# IO.net
KiCad netlist of a schematic drawn in Altium Designer
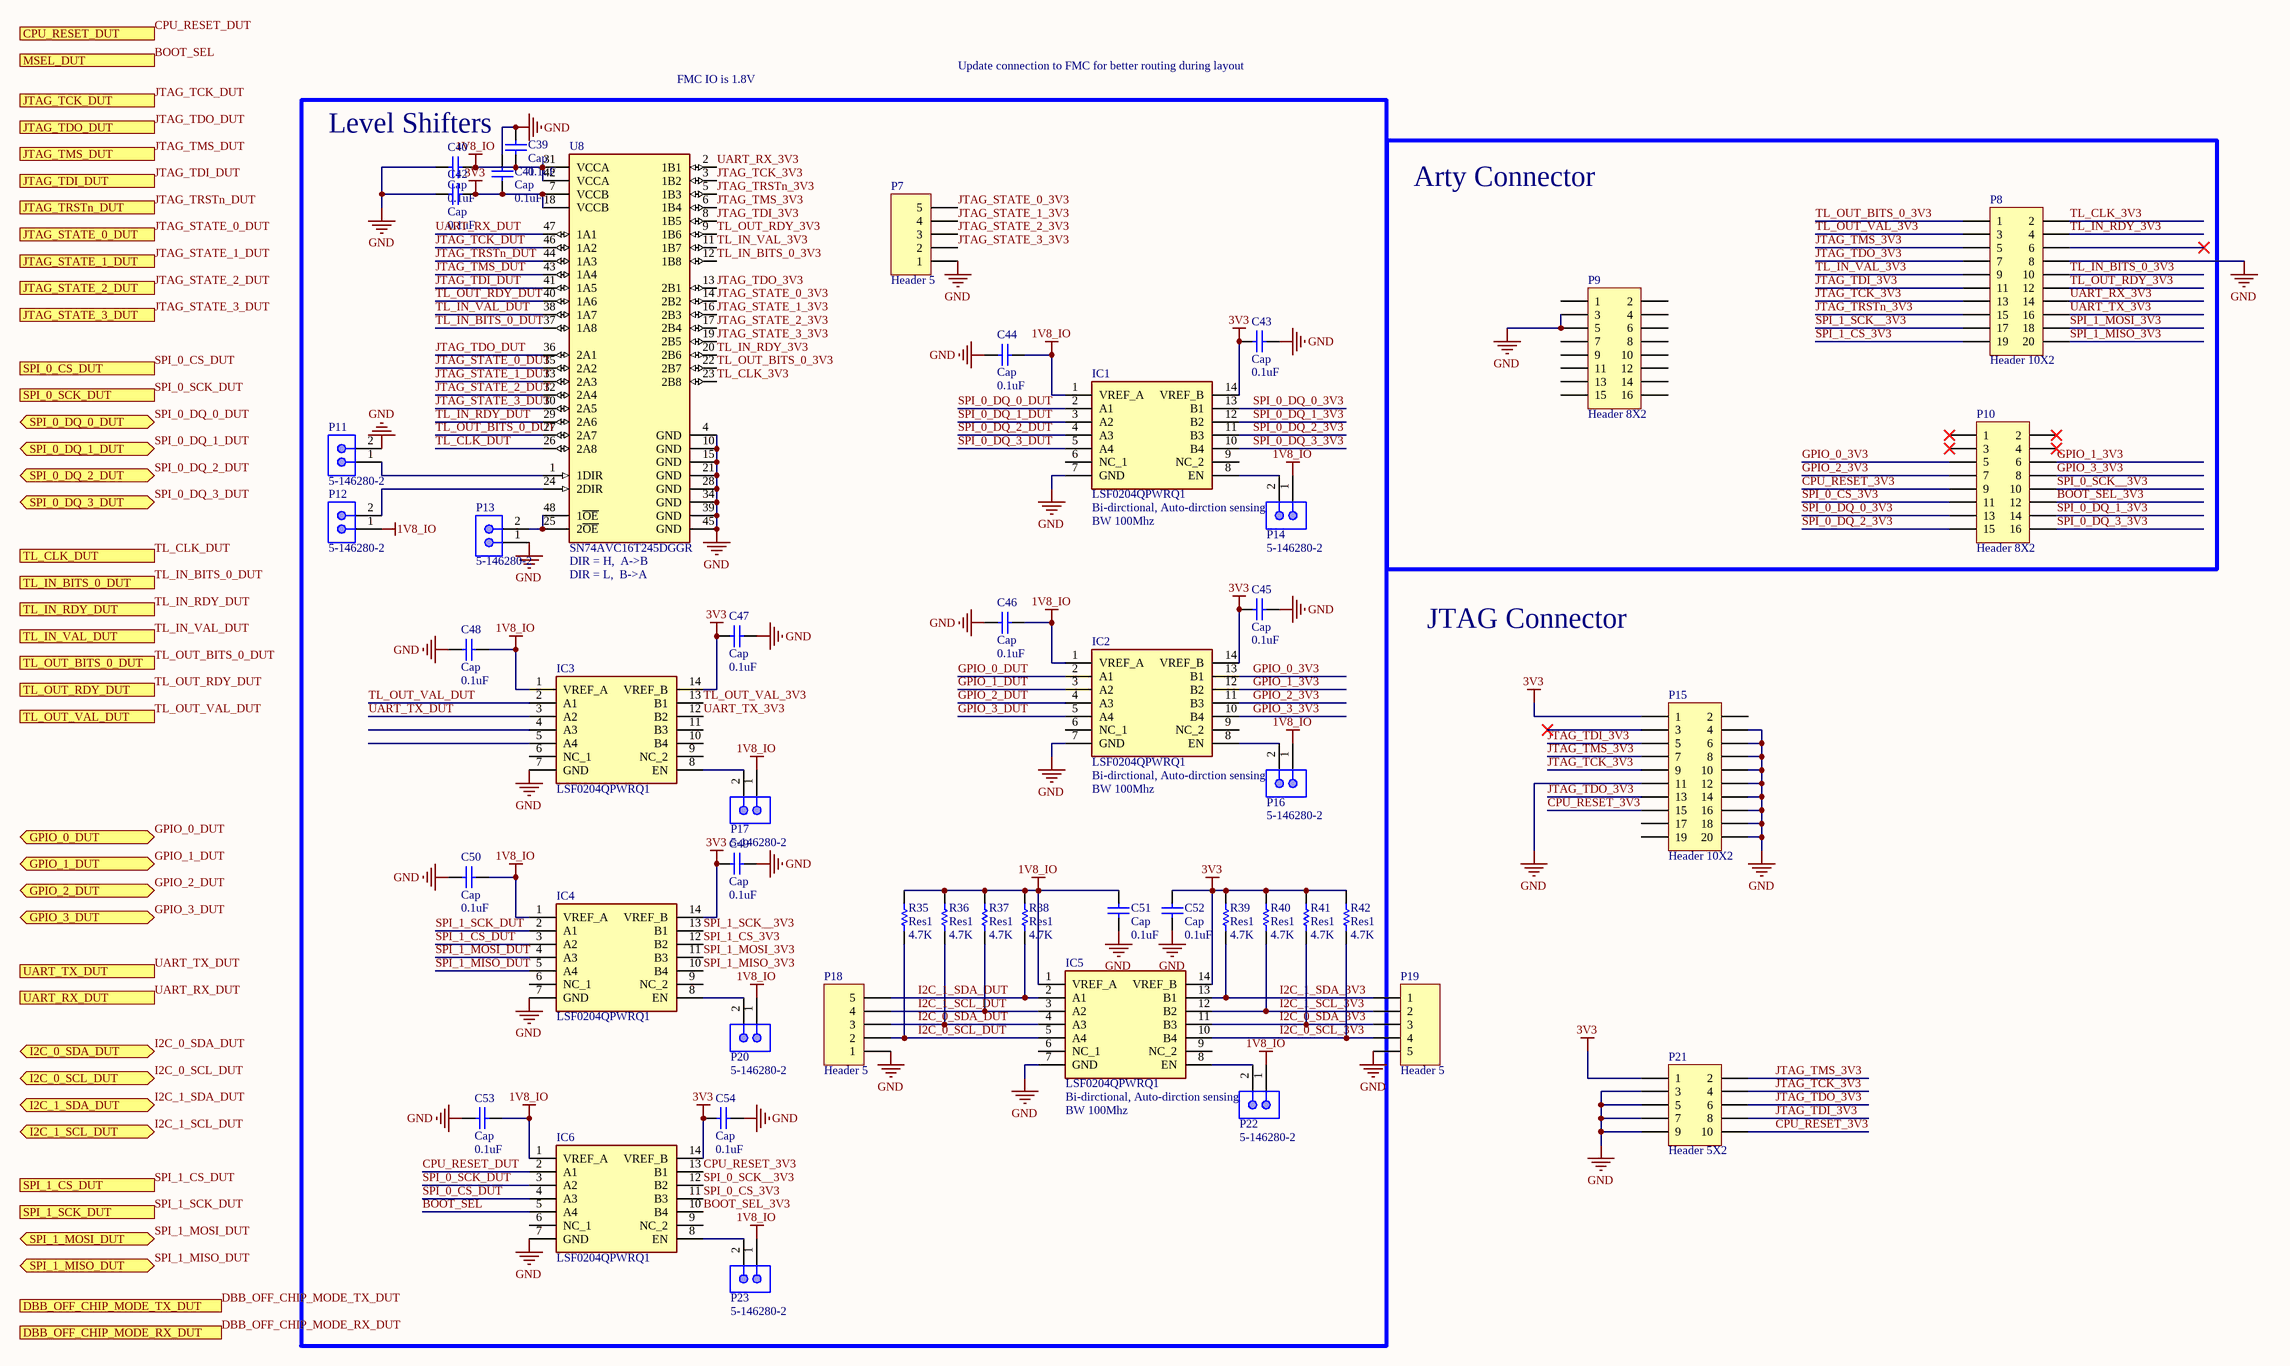
[diagram p0: IO.SchDoc]

(export (version "E")
  (design (tool "Eeschema 10.0.6"))
  (components
    (comp (ref "C39")
      (value "Cap")
      (footprint "0603")
      (description "Capacitor")
      (fields (field (name "ALTIUM_VALUE") "0.1uF") (field (name "PUBLISHER") "Altium Limited"))
      (libsource (lib "Miscellaneous Devices") (part "Cap"))
    )
    (comp (ref "C40")
      (value "Cap")
      (footprint "0603")
      (description "Capacitor")
      (fields (field (name "ALTIUM_VALUE") "0.1uF") (field (name "PUBLISHER") "Altium Limited"))
      (libsource (lib "Miscellaneous Devices") (part "Cap"))
    )
    (comp (ref "C41")
      (value "Cap")
      (footprint "0603")
      (description "Capacitor")
      (fields (field (name "ALTIUM_VALUE") "0.1uF") (field (name "PUBLISHER") "Altium Limited"))
      (libsource (lib "Miscellaneous Devices") (part "Cap"))
    )
    (comp (ref "C42")
      (value "Cap")
      (footprint "0603")
      (description "Capacitor")
      (fields (field (name "ALTIUM_VALUE") "0.1uF") (field (name "PUBLISHER") "Altium Limited"))
      (libsource (lib "Miscellaneous Devices") (part "Cap"))
    )
    (comp (ref "C43")
      (value "Cap")
      (footprint "0603")
      (description "Capacitor")
      (fields (field (name "ALTIUM_VALUE") "0.1uF") (field (name "PUBLISHER") "Altium Limited"))
      (libsource (lib "Miscellaneous Devices") (part "Cap"))
    )
    (comp (ref "C44")
      (value "Cap")
      (footprint "0603")
      (description "Capacitor")
      (fields (field (name "ALTIUM_VALUE") "0.1uF") (field (name "PUBLISHER") "Altium Limited"))
      (libsource (lib "Miscellaneous Devices") (part "Cap"))
    )
    (comp (ref "C45")
      (value "Cap")
      (footprint "0603")
      (description "Capacitor")
      (fields (field (name "ALTIUM_VALUE") "0.1uF") (field (name "PUBLISHER") "Altium Limited"))
      (libsource (lib "Miscellaneous Devices") (part "Cap"))
    )
    (comp (ref "C46")
      (value "Cap")
      (footprint "0603")
      (description "Capacitor")
      (fields (field (name "ALTIUM_VALUE") "0.1uF") (field (name "PUBLISHER") "Altium Limited"))
      (libsource (lib "Miscellaneous Devices") (part "Cap"))
    )
    (comp (ref "C47")
      (value "Cap")
      (footprint "0603")
      (description "Capacitor")
      (fields (field (name "ALTIUM_VALUE") "0.1uF") (field (name "PUBLISHER") "Altium Limited"))
      (libsource (lib "Miscellaneous Devices") (part "Cap"))
    )
    (comp (ref "C48")
      (value "Cap")
      (footprint "0603")
      (description "Capacitor")
      (fields (field (name "ALTIUM_VALUE") "0.1uF") (field (name "PUBLISHER") "Altium Limited"))
      (libsource (lib "Miscellaneous Devices") (part "Cap"))
    )
    (comp (ref "C49")
      (value "Cap")
      (footprint "0603")
      (description "Capacitor")
      (fields (field (name "ALTIUM_VALUE") "0.1uF") (field (name "PUBLISHER") "Altium Limited"))
      (libsource (lib "Miscellaneous Devices") (part "Cap"))
    )
    (comp (ref "C50")
      (value "Cap")
      (footprint "0603")
      (description "Capacitor")
      (fields (field (name "ALTIUM_VALUE") "0.1uF") (field (name "PUBLISHER") "Altium Limited"))
      (libsource (lib "Miscellaneous Devices") (part "Cap"))
    )
    (comp (ref "C51")
      (value "Cap")
      (footprint "0603")
      (description "Capacitor")
      (fields (field (name "ALTIUM_VALUE") "0.1uF") (field (name "PUBLISHER") "Altium Limited"))
      (libsource (lib "Miscellaneous Devices") (part "Cap"))
    )
    (comp (ref "C52")
      (value "Cap")
      (footprint "0603")
      (description "Capacitor")
      (fields (field (name "ALTIUM_VALUE") "0.1uF") (field (name "PUBLISHER") "Altium Limited"))
      (libsource (lib "Miscellaneous Devices") (part "Cap"))
    )
    (comp (ref "C53")
      (value "Cap")
      (footprint "0603")
      (description "Capacitor")
      (fields (field (name "ALTIUM_VALUE") "0.1uF") (field (name "PUBLISHER") "Altium Limited"))
      (libsource (lib "Miscellaneous Devices") (part "Cap"))
    )
    (comp (ref "C54")
      (value "Cap")
      (footprint "0603")
      (description "Capacitor")
      (fields (field (name "ALTIUM_VALUE") "0.1uF") (field (name "PUBLISHER") "Altium Limited"))
      (libsource (lib "Miscellaneous Devices") (part "Cap"))
    )
    (comp (ref "IC1")
      (value "LSF0204QPWRQ1")
      (footprint "SOP65P640X120-14N")
      (fields (field (name "MOUSER PART NUMBER") "595-LSF0204QPWRQ1"))
      (libsource (lib "EE194 Fall2022") (part "LSF0204QPWRQ1"))
    )
    (comp (ref "IC2")
      (value "LSF0204QPWRQ1")
      (footprint "SOP65P640X120-14N")
      (fields (field (name "MOUSER PART NUMBER") "595-LSF0204QPWRQ1"))
      (libsource (lib "EE194 Fall2022") (part "LSF0204QPWRQ1"))
    )
    (comp (ref "IC3")
      (value "LSF0204QPWRQ1")
      (footprint "SOP65P640X120-14N")
      (fields (field (name "MOUSER PART NUMBER") "595-LSF0204QPWRQ1"))
      (libsource (lib "EE194 Fall2022") (part "LSF0204QPWRQ1"))
    )
    (comp (ref "IC4")
      (value "LSF0204QPWRQ1")
      (footprint "SOP65P640X120-14N")
      (fields (field (name "MOUSER PART NUMBER") "595-LSF0204QPWRQ1"))
      (libsource (lib "EE194 Fall2022") (part "LSF0204QPWRQ1"))
    )
    (comp (ref "IC5")
      (value "LSF0204QPWRQ1")
      (footprint "SOP65P640X120-14N")
      (fields (field (name "MOUSER PART NUMBER") "595-LSF0204QPWRQ1"))
      (libsource (lib "EE194 Fall2022") (part "LSF0204QPWRQ1"))
    )
    (comp (ref "IC6")
      (value "LSF0204QPWRQ1")
      (footprint "SOP65P640X120-14N")
      (fields (field (name "MOUSER PART NUMBER") "595-LSF0204QPWRQ1"))
      (libsource (lib "EE194 Fall2022") (part "LSF0204QPWRQ1"))
    )
    (comp (ref "P7")
      (value "Header 5")
      (footprint "HDR1X5")
      (description "Header, 5-Pin")
      (fields (field (name "PUBLISHER") "Altium Limited"))
      (libsource (lib "") (part "Header 5_1"))
    )
    (comp (ref "P8")
      (value "Header 10X2")
      (footprint "HDR2X10")
      (description "Header, 10-Pin, Dual row")
      (fields (field (name "PUBLISHER") "Altium Limited"))
      (libsource (lib "Miscellaneous Connectors") (part "Header 10X2"))
    )
    (comp (ref "P9")
      (value "Header 8X2")
      (footprint "HDR2X8")
      (description "Header, 8-Pin, Dual row")
      (fields (field (name "PUBLISHER") "Altium Limited"))
      (libsource (lib "Miscellaneous Connectors") (part "Header 8X2"))
    )
    (comp (ref "P10")
      (value "Header 8X2")
      (footprint "HDR2X8")
      (description "Header, 8-Pin, Dual row")
      (fields (field (name "PUBLISHER") "Altium Limited"))
      (libsource (lib "Miscellaneous Connectors") (part "Header 8X2"))
    )
    (comp (ref "P11")
      (value "5-146280-2")
      (footprint "TECO-5-146280-2_V")
      (fields (field (name "MANUFACTURER") "TE Connectivity"))
      (libsource (lib "") (part "CN-1P-M-R2_1"))
    )
    (comp (ref "P12")
      (value "5-146280-2")
      (footprint "TECO-5-146280-2_V")
      (fields (field (name "MANUFACTURER") "TE Connectivity"))
      (libsource (lib "") (part "CN-1P-M-R2_1"))
    )
    (comp (ref "P13")
      (value "5-146280-2")
      (footprint "TECO-5-146280-2_V")
      (fields (field (name "MANUFACTURER") "TE Connectivity"))
      (libsource (lib "") (part "CN-1P-M-R2_1"))
    )
    (comp (ref "P14")
      (value "5-146280-2")
      (footprint "TECO-5-146280-2_V")
      (fields (field (name "MANUFACTURER") "TE Connectivity"))
      (libsource (lib "Altium Content Vault") (part "CN-1P-M-R2"))
    )
    (comp (ref "P15")
      (value "Header 10X2")
      (footprint "HDR2X10")
      (description "Header, 10-Pin, Dual row")
      (fields (field (name "PUBLISHER") "Altium Limited"))
      (libsource (lib "Miscellaneous Connectors") (part "Header 10X2"))
    )
    (comp (ref "P16")
      (value "5-146280-2")
      (footprint "TECO-5-146280-2_V")
      (fields (field (name "MANUFACTURER") "TE Connectivity"))
      (libsource (lib "Altium Content Vault") (part "CN-1P-M-R2"))
    )
    (comp (ref "P17")
      (value "5-146280-2")
      (footprint "TECO-5-146280-2_V")
      (fields (field (name "MANUFACTURER") "TE Connectivity"))
      (libsource (lib "Altium Content Vault") (part "CN-1P-M-R2"))
    )
    (comp (ref "P18")
      (value "Header 5")
      (footprint "HDR1X5")
      (description "Header, 5-Pin")
      (fields (field (name "PUBLISHER") "Altium Limited"))
      (libsource (lib "") (part "Header 5_1"))
    )
    (comp (ref "P19")
      (value "Header 5")
      (footprint "HDR1X5")
      (description "Header, 5-Pin")
      (fields (field (name "PUBLISHER") "Altium Limited"))
      (libsource (lib "Miscellaneous Connectors") (part "Header 5"))
    )
    (comp (ref "P20")
      (value "5-146280-2")
      (footprint "TECO-5-146280-2_V")
      (fields (field (name "MANUFACTURER") "TE Connectivity"))
      (libsource (lib "Altium Content Vault") (part "CN-1P-M-R2"))
    )
    (comp (ref "P21")
      (value "Header 5X2")
      (footprint "HDR2X5")
      (description "Header, 5-Pin, Dual row")
      (fields (field (name "PUBLISHER") "Altium Limited"))
      (libsource (lib "Miscellaneous Connectors") (part "Header 5X2"))
    )
    (comp (ref "P22")
      (value "5-146280-2")
      (footprint "TECO-5-146280-2_V")
      (fields (field (name "MANUFACTURER") "TE Connectivity"))
      (libsource (lib "Altium Content Vault") (part "CN-1P-M-R2"))
    )
    (comp (ref "P23")
      (value "5-146280-2")
      (footprint "TECO-5-146280-2_V")
      (fields (field (name "MANUFACTURER") "TE Connectivity"))
      (libsource (lib "Altium Content Vault") (part "CN-1P-M-R2"))
    )
    (comp (ref "R35")
      (value "Res1")
      (footprint "0603")
      (description "Resistor")
      (fields (field (name "ALTIUM_VALUE") "4.7K") (field (name "PUBLISHER") "Altium Limited"))
      (libsource (lib "Miscellaneous Devices") (part "Res1"))
    )
    (comp (ref "R36")
      (value "Res1")
      (footprint "0603")
      (description "Resistor")
      (fields (field (name "ALTIUM_VALUE") "4.7K") (field (name "PUBLISHER") "Altium Limited"))
      (libsource (lib "Miscellaneous Devices") (part "Res1"))
    )
    (comp (ref "R37")
      (value "Res1")
      (footprint "0603")
      (description "Resistor")
      (fields (field (name "ALTIUM_VALUE") "4.7K") (field (name "PUBLISHER") "Altium Limited"))
      (libsource (lib "Miscellaneous Devices") (part "Res1"))
    )
    (comp (ref "R38")
      (value "Res1")
      (footprint "0603")
      (description "Resistor")
      (fields (field (name "ALTIUM_VALUE") "4.7K") (field (name "PUBLISHER") "Altium Limited"))
      (libsource (lib "Miscellaneous Devices") (part "Res1"))
    )
    (comp (ref "R39")
      (value "Res1")
      (footprint "0603")
      (description "Resistor")
      (fields (field (name "ALTIUM_VALUE") "4.7K") (field (name "PUBLISHER") "Altium Limited"))
      (libsource (lib "Miscellaneous Devices") (part "Res1"))
    )
    (comp (ref "R40")
      (value "Res1")
      (footprint "0603")
      (description "Resistor")
      (fields (field (name "ALTIUM_VALUE") "4.7K") (field (name "PUBLISHER") "Altium Limited"))
      (libsource (lib "Miscellaneous Devices") (part "Res1"))
    )
    (comp (ref "R41")
      (value "Res1")
      (footprint "0603")
      (description "Resistor")
      (fields (field (name "ALTIUM_VALUE") "4.7K") (field (name "PUBLISHER") "Altium Limited"))
      (libsource (lib "Miscellaneous Devices") (part "Res1"))
    )
    (comp (ref "R42")
      (value "Res1")
      (footprint "0603")
      (description "Resistor")
      (fields (field (name "ALTIUM_VALUE") "4.7K") (field (name "PUBLISHER") "Altium Limited"))
      (libsource (lib "Miscellaneous Devices") (part "Res1"))
    )
    (comp (ref "U8")
      (value "SN74AVC16T245DGGR")
      (footprint "FP-DGG0048A-IPC_B")
      (description "IC TRNSLTR BIDIRECTIONAL 48TSSOP")
      (libsource (lib "Altium Content Vault") (part "fd802b0a97c1d21cd49c17e76ee5822"))
    )
  )
  (nets
    (net (code "2") (name "/BOOT_SEL") (class "Default")
      (node (ref "IC6") (pin "5") (pinfunction "A4_5") (pintype "passive"))
    )
    (net (code "3") (name "/BOOT_SEL_3V3") (class "Default")
      (node (ref "IC6") (pin "10") (pinfunction "B4_10") (pintype "passive"))
      (node (ref "P10") (pin "12") (pinfunction "12_12") (pintype "passive"))
    )
    (net (code "4") (name "/CPU_RESET_3V3") (class "Default")
      (node (ref "IC6") (pin "13") (pinfunction "B1_13") (pintype "passive"))
      (node (ref "P10") (pin "9") (pinfunction "9_9") (pintype "passive"))
      (node (ref "P15") (pin "15") (pinfunction "15_15") (pintype "passive"))
      (node (ref "P21") (pin "10") (pinfunction "10_10") (pintype "passive"))
    )
    (net (code "5") (name "/CPU_RESET_DUT") (class "Default")
      (node (ref "IC6") (pin "2") (pinfunction "A1_2") (pintype "passive"))
    )
    (net (code "8") (name "/GPIO_0_3V3") (class "Default")
      (node (ref "IC2") (pin "13") (pinfunction "B1_13") (pintype "passive"))
      (node (ref "P10") (pin "5") (pinfunction "5_5") (pintype "passive"))
    )
    (net (code "9") (name "/GPIO_0_DUT") (class "Default")
      (node (ref "IC2") (pin "2") (pinfunction "A1_2") (pintype "passive"))
    )
    (net (code "10") (name "/GPIO_1_3V3") (class "Default")
      (node (ref "IC2") (pin "12") (pinfunction "B2_12") (pintype "passive"))
      (node (ref "P10") (pin "6") (pinfunction "6_6") (pintype "passive"))
    )
    (net (code "11") (name "/GPIO_1_DUT") (class "Default")
      (node (ref "IC2") (pin "3") (pinfunction "A2_3") (pintype "passive"))
    )
    (net (code "12") (name "/GPIO_2_3V3") (class "Default")
      (node (ref "IC2") (pin "11") (pinfunction "B3_11") (pintype "passive"))
      (node (ref "P10") (pin "7") (pinfunction "7_7") (pintype "passive"))
    )
    (net (code "13") (name "/GPIO_2_DUT") (class "Default")
      (node (ref "IC2") (pin "4") (pinfunction "A3_4") (pintype "passive"))
    )
    (net (code "14") (name "/GPIO_3_3V3") (class "Default")
      (node (ref "IC2") (pin "10") (pinfunction "B4_10") (pintype "passive"))
      (node (ref "P10") (pin "8") (pinfunction "8_8") (pintype "passive"))
    )
    (net (code "15") (name "/GPIO_3_DUT") (class "Default")
      (node (ref "IC2") (pin "5") (pinfunction "A4_5") (pintype "passive"))
    )
    (net (code "16") (name "/I2C_0_SCL_3V3") (class "Default")
      (node (ref "IC5") (pin "10") (pinfunction "B4_10") (pintype "passive"))
      (node (ref "P19") (pin "4") (pinfunction "4_4") (pintype "passive"))
      (node (ref "R42") (pin "1") (pinfunction "1_1") (pintype "passive"))
    )
    (net (code "17") (name "/I2C_0_SCL_DUT") (class "Default")
      (node (ref "IC5") (pin "5") (pinfunction "A4_5") (pintype "passive"))
      (node (ref "P18") (pin "2") (pinfunction "2_2") (pintype "passive"))
      (node (ref "R35") (pin "1") (pinfunction "1_1") (pintype "passive"))
    )
    (net (code "18") (name "/I2C_0_SDA_3V3") (class "Default")
      (node (ref "IC5") (pin "11") (pinfunction "B3_11") (pintype "passive"))
      (node (ref "P19") (pin "3") (pinfunction "3_3") (pintype "passive"))
      (node (ref "R41") (pin "1") (pinfunction "1_1") (pintype "passive"))
    )
    (net (code "19") (name "/I2C_0_SDA_DUT") (class "Default")
      (node (ref "IC5") (pin "4") (pinfunction "A3_4") (pintype "passive"))
      (node (ref "P18") (pin "3") (pinfunction "3_3") (pintype "passive"))
      (node (ref "R36") (pin "1") (pinfunction "1_1") (pintype "passive"))
    )
    (net (code "20") (name "/I2C_1_SCL_3V3") (class "Default")
      (node (ref "IC5") (pin "12") (pinfunction "B2_12") (pintype "passive"))
      (node (ref "P19") (pin "2") (pinfunction "2_2") (pintype "passive"))
      (node (ref "R40") (pin "1") (pinfunction "1_1") (pintype "passive"))
    )
    (net (code "21") (name "/I2C_1_SCL_DUT") (class "Default")
      (node (ref "IC5") (pin "3") (pinfunction "A2_3") (pintype "passive"))
      (node (ref "P18") (pin "4") (pinfunction "4_4") (pintype "passive"))
      (node (ref "R37") (pin "1") (pinfunction "1_1") (pintype "passive"))
    )
    (net (code "22") (name "/I2C_1_SDA_3V3") (class "Default")
      (node (ref "IC5") (pin "13") (pinfunction "B1_13") (pintype "passive"))
      (node (ref "P19") (pin "1") (pinfunction "1_1") (pintype "passive"))
      (node (ref "R39") (pin "1") (pinfunction "1_1") (pintype "passive"))
    )
    (net (code "23") (name "/I2C_1_SDA_DUT") (class "Default")
      (node (ref "IC5") (pin "2") (pinfunction "A1_2") (pintype "passive"))
      (node (ref "P18") (pin "5") (pinfunction "5_5") (pintype "passive"))
      (node (ref "R38") (pin "1") (pinfunction "1_1") (pintype "passive"))
    )
    (net (code "24") (name "/JTAG_STATE_0_3V3") (class "Default")
      (node (ref "P7") (pin "5") (pinfunction "5_5") (pintype "passive"))
      (node (ref "U8") (pin "14") (pinfunction "2B2_14") (pintype "bidirectional"))
    )
    (net (code "25") (name "/JTAG_STATE_0_DUT") (class "Default")
      (node (ref "U8") (pin "35") (pinfunction "2A2_35") (pintype "bidirectional"))
    )
    (net (code "26") (name "/JTAG_STATE_1_3V3") (class "Default")
      (node (ref "P7") (pin "4") (pinfunction "4_4") (pintype "passive"))
      (node (ref "U8") (pin "16") (pinfunction "2B3_16") (pintype "bidirectional"))
    )
    (net (code "27") (name "/JTAG_STATE_1_DUT") (class "Default")
      (node (ref "U8") (pin "33") (pinfunction "2A3_33") (pintype "bidirectional"))
    )
    (net (code "28") (name "/JTAG_STATE_2_3V3") (class "Default")
      (node (ref "P7") (pin "3") (pinfunction "3_3") (pintype "passive"))
      (node (ref "U8") (pin "17") (pinfunction "2B4_17") (pintype "bidirectional"))
    )
    (net (code "29") (name "/JTAG_STATE_2_DUT") (class "Default")
      (node (ref "U8") (pin "32") (pinfunction "2A4_32") (pintype "bidirectional"))
    )
    (net (code "30") (name "/JTAG_STATE_3_3V3") (class "Default")
      (node (ref "P7") (pin "2") (pinfunction "2_2") (pintype "passive"))
      (node (ref "U8") (pin "19") (pinfunction "2B5_19") (pintype "bidirectional"))
    )
    (net (code "31") (name "/JTAG_STATE_3_DUT") (class "Default")
      (node (ref "U8") (pin "30") (pinfunction "2A5_30") (pintype "bidirectional"))
    )
    (net (code "32") (name "/JTAG_TCK_3V3") (class "Default")
      (node (ref "P15") (pin "9") (pinfunction "9_9") (pintype "passive"))
      (node (ref "P21") (pin "4") (pinfunction "4_4") (pintype "passive"))
      (node (ref "P8") (pin "13") (pinfunction "13_13") (pintype "passive"))
      (node (ref "U8") (pin "3") (pinfunction "1B2_3") (pintype "bidirectional"))
    )
    (net (code "33") (name "/JTAG_TCK_DUT") (class "Default")
      (node (ref "U8") (pin "46") (pinfunction "1A2_46") (pintype "bidirectional"))
    )
    (net (code "34") (name "/JTAG_TDI_3V3") (class "Default")
      (node (ref "P15") (pin "5") (pinfunction "5_5") (pintype "passive"))
      (node (ref "P21") (pin "8") (pinfunction "8_8") (pintype "passive"))
      (node (ref "P8") (pin "11") (pinfunction "11_11") (pintype "passive"))
      (node (ref "U8") (pin "8") (pinfunction "1B5_8") (pintype "bidirectional"))
    )
    (net (code "35") (name "/JTAG_TDI_DUT") (class "Default")
      (node (ref "U8") (pin "41") (pinfunction "1A5_41") (pintype "bidirectional"))
    )
    (net (code "36") (name "/JTAG_TDO_3V3") (class "Default")
      (node (ref "P15") (pin "13") (pinfunction "13_13") (pintype "passive"))
      (node (ref "P21") (pin "6") (pinfunction "6_6") (pintype "passive"))
      (node (ref "P8") (pin "7") (pinfunction "7_7") (pintype "passive"))
      (node (ref "U8") (pin "13") (pinfunction "2B1_13") (pintype "bidirectional"))
    )
    (net (code "37") (name "/JTAG_TDO_DUT") (class "Default")
      (node (ref "U8") (pin "36") (pinfunction "2A1_36") (pintype "bidirectional"))
    )
    (net (code "38") (name "/JTAG_TMS_3V3") (class "Default")
      (node (ref "P15") (pin "7") (pinfunction "7_7") (pintype "passive"))
      (node (ref "P21") (pin "2") (pinfunction "2_2") (pintype "passive"))
      (node (ref "P8") (pin "5") (pinfunction "5_5") (pintype "passive"))
      (node (ref "U8") (pin "6") (pinfunction "1B4_6") (pintype "bidirectional"))
    )
    (net (code "39") (name "/JTAG_TMS_DUT") (class "Default")
      (node (ref "U8") (pin "43") (pinfunction "1A4_43") (pintype "bidirectional"))
    )
    (net (code "40") (name "/JTAG_TRSTn_3V3") (class "Default")
      (node (ref "P8") (pin "15") (pinfunction "15_15") (pintype "passive"))
      (node (ref "U8") (pin "5") (pinfunction "1B3_5") (pintype "bidirectional"))
    )
    (net (code "41") (name "/JTAG_TRSTn_DUT") (class "Default")
      (node (ref "U8") (pin "44") (pinfunction "1A3_44") (pintype "bidirectional"))
    )
    (net (code "42") (name "/SPI_0_CS_3V3") (class "Default")
      (node (ref "IC6") (pin "11") (pinfunction "B3_11") (pintype "passive"))
      (node (ref "P10") (pin "11") (pinfunction "11_11") (pintype "passive"))
    )
    (net (code "43") (name "/SPI_0_CS_DUT") (class "Default")
      (node (ref "IC6") (pin "4") (pinfunction "A3_4") (pintype "passive"))
    )
    (net (code "44") (name "/SPI_0_DQ_0_3V3") (class "Default")
      (node (ref "IC1") (pin "13") (pinfunction "B1_13") (pintype "passive"))
      (node (ref "P10") (pin "13") (pinfunction "13_13") (pintype "passive"))
    )
    (net (code "45") (name "/SPI_0_DQ_0_DUT") (class "Default")
      (node (ref "IC1") (pin "2") (pinfunction "A1_2") (pintype "passive"))
    )
    (net (code "46") (name "/SPI_0_DQ_1_3V3") (class "Default")
      (node (ref "IC1") (pin "12") (pinfunction "B2_12") (pintype "passive"))
      (node (ref "P10") (pin "14") (pinfunction "14_14") (pintype "passive"))
    )
    (net (code "47") (name "/SPI_0_DQ_1_DUT") (class "Default")
      (node (ref "IC1") (pin "3") (pinfunction "A2_3") (pintype "passive"))
    )
    (net (code "48") (name "/SPI_0_DQ_2_3V3") (class "Default")
      (node (ref "IC1") (pin "11") (pinfunction "B3_11") (pintype "passive"))
      (node (ref "P10") (pin "15") (pinfunction "15_15") (pintype "passive"))
    )
    (net (code "49") (name "/SPI_0_DQ_2_DUT") (class "Default")
      (node (ref "IC1") (pin "4") (pinfunction "A3_4") (pintype "passive"))
    )
    (net (code "50") (name "/SPI_0_DQ_3_3V3") (class "Default")
      (node (ref "IC1") (pin "10") (pinfunction "B4_10") (pintype "passive"))
      (node (ref "P10") (pin "16") (pinfunction "16_16") (pintype "passive"))
    )
    (net (code "51") (name "/SPI_0_DQ_3_DUT") (class "Default")
      (node (ref "IC1") (pin "5") (pinfunction "A4_5") (pintype "passive"))
    )
    (net (code "52") (name "/SPI_0_SCK_DUT") (class "Default")
      (node (ref "IC6") (pin "3") (pinfunction "A2_3") (pintype "passive"))
    )
    (net (code "53") (name "/SPI_0_SCK__3V3") (class "Default")
      (node (ref "IC6") (pin "12") (pinfunction "B2_12") (pintype "passive"))
      (node (ref "P10") (pin "10") (pinfunction "10_10") (pintype "passive"))
    )
    (net (code "54") (name "/SPI_1_CS_3V3") (class "Default")
      (node (ref "IC4") (pin "12") (pinfunction "B2_12") (pintype "passive"))
      (node (ref "P8") (pin "19") (pinfunction "19_19") (pintype "passive"))
    )
    (net (code "55") (name "/SPI_1_CS_DUT") (class "Default")
      (node (ref "IC4") (pin "3") (pinfunction "A2_3") (pintype "passive"))
    )
    (net (code "56") (name "/SPI_1_MISO_3V3") (class "Default")
      (node (ref "IC4") (pin "10") (pinfunction "B4_10") (pintype "passive"))
      (node (ref "P8") (pin "20") (pinfunction "20_20") (pintype "passive"))
    )
    (net (code "57") (name "/SPI_1_MISO_DUT") (class "Default")
      (node (ref "IC4") (pin "5") (pinfunction "A4_5") (pintype "passive"))
    )
    (net (code "58") (name "/SPI_1_MOSI_3V3") (class "Default")
      (node (ref "IC4") (pin "11") (pinfunction "B3_11") (pintype "passive"))
      (node (ref "P8") (pin "18") (pinfunction "18_18") (pintype "passive"))
    )
    (net (code "59") (name "/SPI_1_MOSI_DUT") (class "Default")
      (node (ref "IC4") (pin "4") (pinfunction "A3_4") (pintype "passive"))
    )
    (net (code "60") (name "/SPI_1_SCK_DUT") (class "Default")
      (node (ref "IC4") (pin "2") (pinfunction "A1_2") (pintype "passive"))
    )
    (net (code "61") (name "/SPI_1_SCK__3V3") (class "Default")
      (node (ref "IC4") (pin "13") (pinfunction "B1_13") (pintype "passive"))
      (node (ref "P8") (pin "17") (pinfunction "17_17") (pintype "passive"))
    )
    (net (code "62") (name "/TL_CLK_3V3") (class "Default")
      (node (ref "P8") (pin "2") (pinfunction "2_2") (pintype "passive"))
      (node (ref "U8") (pin "23") (pinfunction "2B8_23") (pintype "bidirectional"))
    )
    (net (code "63") (name "/TL_CLK_DUT") (class "Default")
      (node (ref "U8") (pin "26") (pinfunction "2A8_26") (pintype "bidirectional"))
    )
    (net (code "64") (name "/TL_IN_BITS_0_3V3") (class "Default")
      (node (ref "P8") (pin "10") (pinfunction "10_10") (pintype "passive"))
      (node (ref "U8") (pin "12") (pinfunction "1B8_12") (pintype "bidirectional"))
    )
    (net (code "65") (name "/TL_IN_BITS_0_DUT") (class "Default")
      (node (ref "U8") (pin "37") (pinfunction "1A8_37") (pintype "bidirectional"))
    )
    (net (code "66") (name "/TL_IN_RDY_3V3") (class "Default")
      (node (ref "P8") (pin "4") (pinfunction "4_4") (pintype "passive"))
      (node (ref "U8") (pin "20") (pinfunction "2B6_20") (pintype "bidirectional"))
    )
    (net (code "67") (name "/TL_IN_RDY_DUT") (class "Default")
      (node (ref "U8") (pin "29") (pinfunction "2A6_29") (pintype "bidirectional"))
    )
    (net (code "68") (name "/TL_IN_VAL_3V3") (class "Default")
      (node (ref "P8") (pin "9") (pinfunction "9_9") (pintype "passive"))
      (node (ref "U8") (pin "11") (pinfunction "1B7_11") (pintype "bidirectional"))
    )
    (net (code "69") (name "/TL_IN_VAL_DUT") (class "Default")
      (node (ref "U8") (pin "38") (pinfunction "1A7_38") (pintype "bidirectional"))
    )
    (net (code "70") (name "/TL_OUT_BITS_0_3V3") (class "Default")
      (node (ref "P8") (pin "1") (pinfunction "1_1") (pintype "passive"))
      (node (ref "U8") (pin "22") (pinfunction "2B7_22") (pintype "bidirectional"))
    )
    (net (code "71") (name "/TL_OUT_BITS_0_DUT") (class "Default")
      (node (ref "U8") (pin "27") (pinfunction "2A7_27") (pintype "bidirectional"))
    )
    (net (code "72") (name "/TL_OUT_RDY_3V3") (class "Default")
      (node (ref "P8") (pin "12") (pinfunction "12_12") (pintype "passive"))
      (node (ref "U8") (pin "9") (pinfunction "1B6_9") (pintype "bidirectional"))
    )
    (net (code "73") (name "/TL_OUT_RDY_DUT") (class "Default")
      (node (ref "U8") (pin "40") (pinfunction "1A6_40") (pintype "bidirectional"))
    )
    (net (code "74") (name "/TL_OUT_VAL_3V3") (class "Default")
      (node (ref "IC3") (pin "13") (pinfunction "B1_13") (pintype "passive"))
      (node (ref "P8") (pin "3") (pinfunction "3_3") (pintype "passive"))
    )
    (net (code "75") (name "/TL_OUT_VAL_DUT") (class "Default")
      (node (ref "IC3") (pin "2") (pinfunction "A1_2") (pintype "passive"))
    )
    (net (code "76") (name "/UART_RX_3V3") (class "Default")
      (node (ref "P8") (pin "14") (pinfunction "14_14") (pintype "passive"))
      (node (ref "U8") (pin "2") (pinfunction "1B1_2") (pintype "bidirectional"))
    )
    (net (code "77") (name "/UART_RX_DUT") (class "Default")
      (node (ref "U8") (pin "47") (pinfunction "1A1_47") (pintype "bidirectional"))
    )
    (net (code "78") (name "/UART_TX_3V3") (class "Default")
      (node (ref "IC3") (pin "12") (pinfunction "B2_12") (pintype "passive"))
      (node (ref "P8") (pin "16") (pinfunction "16_16") (pintype "passive"))
    )
    (net (code "79") (name "/UART_TX_DUT") (class "Default")
      (node (ref "IC3") (pin "3") (pinfunction "A2_3") (pintype "passive"))
    )
    (net (code "80") (name "1V8_IO") (class "Default")
      (node (ref "C39") (pin "2") (pinfunction "2_2") (pintype "passive"))
      (node (ref "C40") (pin "1") (pinfunction "1_1") (pintype "passive"))
      (node (ref "C44") (pin "1") (pinfunction "1_1") (pintype "passive"))
      (node (ref "C46") (pin "1") (pinfunction "1_1") (pintype "passive"))
      (node (ref "C48") (pin "1") (pinfunction "1_1") (pintype "passive"))
      (node (ref "C50") (pin "1") (pinfunction "1_1") (pintype "passive"))
      (node (ref "C51") (pin "2") (pinfunction "2_2") (pintype "passive"))
      (node (ref "C53") (pin "1") (pinfunction "1_1") (pintype "passive"))
      (node (ref "IC1") (pin "1") (pinfunction "VREF_A_1") (pintype "passive"))
      (node (ref "IC2") (pin "1") (pinfunction "VREF_A_1") (pintype "passive"))
      (node (ref "IC3") (pin "1") (pinfunction "VREF_A_1") (pintype "passive"))
      (node (ref "IC4") (pin "1") (pinfunction "VREF_A_1") (pintype "passive"))
      (node (ref "IC5") (pin "1") (pinfunction "VREF_A_1") (pintype "passive"))
      (node (ref "IC6") (pin "1") (pinfunction "VREF_A_1") (pintype "passive"))
      (node (ref "P12") (pin "1") (pinfunction "1_1") (pintype "passive"))
      (node (ref "P14") (pin "1") (pinfunction "1_1") (pintype "passive"))
      (node (ref "P16") (pin "1") (pinfunction "1_1") (pintype "passive"))
      (node (ref "P17") (pin "1") (pinfunction "1_1") (pintype "passive"))
      (node (ref "P20") (pin "1") (pinfunction "1_1") (pintype "passive"))
      (node (ref "P22") (pin "1") (pinfunction "1_1") (pintype "passive"))
      (node (ref "P23") (pin "1") (pinfunction "1_1") (pintype "passive"))
      (node (ref "R35") (pin "2") (pinfunction "2_2") (pintype "passive"))
      (node (ref "R36") (pin "2") (pinfunction "2_2") (pintype "passive"))
      (node (ref "R37") (pin "2") (pinfunction "2_2") (pintype "passive"))
      (node (ref "R38") (pin "2") (pinfunction "2_2") (pintype "passive"))
      (node (ref "U8") (pin "31") (pinfunction "VCCA_31") (pintype "power_in"))
      (node (ref "U8") (pin "42") (pinfunction "VCCA_42") (pintype "power_in"))
    )
    (net (code "81") (name "3V3") (class "Default")
      (node (ref "C41") (pin "2") (pinfunction "2_2") (pintype "passive"))
      (node (ref "C42") (pin "1") (pinfunction "1_1") (pintype "passive"))
      (node (ref "C43") (pin "2") (pinfunction "2_2") (pintype "passive"))
      (node (ref "C45") (pin "2") (pinfunction "2_2") (pintype "passive"))
      (node (ref "C47") (pin "2") (pinfunction "2_2") (pintype "passive"))
      (node (ref "C49") (pin "2") (pinfunction "2_2") (pintype "passive"))
      (node (ref "C52") (pin "2") (pinfunction "2_2") (pintype "passive"))
      (node (ref "C54") (pin "2") (pinfunction "2_2") (pintype "passive"))
      (node (ref "IC1") (pin "14") (pinfunction "VREF_B_14") (pintype "passive"))
      (node (ref "IC2") (pin "14") (pinfunction "VREF_B_14") (pintype "passive"))
      (node (ref "IC3") (pin "14") (pinfunction "VREF_B_14") (pintype "passive"))
      (node (ref "IC4") (pin "14") (pinfunction "VREF_B_14") (pintype "passive"))
      (node (ref "IC5") (pin "14") (pinfunction "VREF_B_14") (pintype "passive"))
      (node (ref "IC6") (pin "14") (pinfunction "VREF_B_14") (pintype "passive"))
      (node (ref "P15") (pin "1") (pinfunction "1_1") (pintype "passive"))
      (node (ref "P21") (pin "1") (pinfunction "1_1") (pintype "passive"))
      (node (ref "R39") (pin "2") (pinfunction "2_2") (pintype "passive"))
      (node (ref "R40") (pin "2") (pinfunction "2_2") (pintype "passive"))
      (node (ref "R41") (pin "2") (pinfunction "2_2") (pintype "passive"))
      (node (ref "R42") (pin "2") (pinfunction "2_2") (pintype "passive"))
      (node (ref "U8") (pin "18") (pinfunction "VCCB_18") (pintype "power_in"))
      (node (ref "U8") (pin "7") (pinfunction "VCCB_7") (pintype "power_in"))
    )
    (net (code "82") (name "GND") (class "Default")
      (node (ref "C39") (pin "1") (pinfunction "1_1") (pintype "passive"))
      (node (ref "C40") (pin "2") (pinfunction "2_2") (pintype "passive"))
      (node (ref "C41") (pin "1") (pinfunction "1_1") (pintype "passive"))
      (node (ref "C42") (pin "2") (pinfunction "2_2") (pintype "passive"))
      (node (ref "C43") (pin "1") (pinfunction "1_1") (pintype "passive"))
      (node (ref "C44") (pin "2") (pinfunction "2_2") (pintype "passive"))
      (node (ref "C45") (pin "1") (pinfunction "1_1") (pintype "passive"))
      (node (ref "C46") (pin "2") (pinfunction "2_2") (pintype "passive"))
      (node (ref "C47") (pin "1") (pinfunction "1_1") (pintype "passive"))
      (node (ref "C48") (pin "2") (pinfunction "2_2") (pintype "passive"))
      (node (ref "C49") (pin "1") (pinfunction "1_1") (pintype "passive"))
      (node (ref "C50") (pin "2") (pinfunction "2_2") (pintype "passive"))
      (node (ref "C51") (pin "1") (pinfunction "1_1") (pintype "passive"))
      (node (ref "C52") (pin "1") (pinfunction "1_1") (pintype "passive"))
      (node (ref "C53") (pin "2") (pinfunction "2_2") (pintype "passive"))
      (node (ref "C54") (pin "1") (pinfunction "1_1") (pintype "passive"))
      (node (ref "IC1") (pin "7") (pinfunction "GND_7") (pintype "passive"))
      (node (ref "IC2") (pin "7") (pinfunction "GND_7") (pintype "passive"))
      (node (ref "IC3") (pin "7") (pinfunction "GND_7") (pintype "passive"))
      (node (ref "IC4") (pin "7") (pinfunction "GND_7") (pintype "passive"))
      (node (ref "IC5") (pin "7") (pinfunction "GND_7") (pintype "passive"))
      (node (ref "IC6") (pin "7") (pinfunction "GND_7") (pintype "passive"))
      (node (ref "P11") (pin "2") (pinfunction "2_2") (pintype "passive"))
      (node (ref "P13") (pin "1") (pinfunction "1_1") (pintype "passive"))
      (node (ref "P15") (pin "10") (pinfunction "10_10") (pintype "passive"))
      (node (ref "P15") (pin "11") (pinfunction "11_11") (pintype "passive"))
      (node (ref "P15") (pin "12") (pinfunction "12_12") (pintype "passive"))
      (node (ref "P15") (pin "14") (pinfunction "14_14") (pintype "passive"))
      (node (ref "P15") (pin "16") (pinfunction "16_16") (pintype "passive"))
      (node (ref "P15") (pin "18") (pinfunction "18_18") (pintype "passive"))
      (node (ref "P15") (pin "20") (pinfunction "20_20") (pintype "passive"))
      (node (ref "P15") (pin "4") (pinfunction "4_4") (pintype "passive"))
      (node (ref "P15") (pin "6") (pinfunction "6_6") (pintype "passive"))
      (node (ref "P15") (pin "8") (pinfunction "8_8") (pintype "passive"))
      (node (ref "P18") (pin "1") (pinfunction "1_1") (pintype "passive"))
      (node (ref "P19") (pin "5") (pinfunction "5_5") (pintype "passive"))
      (node (ref "P21") (pin "3") (pinfunction "3_3") (pintype "passive"))
      (node (ref "P21") (pin "5") (pinfunction "5_5") (pintype "passive"))
      (node (ref "P21") (pin "7") (pinfunction "7_7") (pintype "passive"))
      (node (ref "P21") (pin "9") (pinfunction "9_9") (pintype "passive"))
      (node (ref "P7") (pin "1") (pinfunction "1_1") (pintype "passive"))
      (node (ref "P8") (pin "8") (pinfunction "8_8") (pintype "passive"))
      (node (ref "P9") (pin "3") (pinfunction "3_3") (pintype "passive"))
      (node (ref "P9") (pin "5") (pinfunction "5_5") (pintype "passive"))
      (node (ref "U8") (pin "10") (pinfunction "GND_10") (pintype "power_in"))
      (node (ref "U8") (pin "15") (pinfunction "GND_15") (pintype "power_in"))
      (node (ref "U8") (pin "21") (pinfunction "GND_21") (pintype "power_in"))
      (node (ref "U8") (pin "28") (pinfunction "GND_28") (pintype "power_in"))
      (node (ref "U8") (pin "34") (pinfunction "GND_34") (pintype "power_in"))
      (node (ref "U8") (pin "39") (pinfunction "GND_39") (pintype "power_in"))
      (node (ref "U8") (pin "4") (pinfunction "GND_4") (pintype "power_in"))
      (node (ref "U8") (pin "45") (pinfunction "GND_45") (pintype "power_in"))
    )
    (net (code "83") (name "Net-(IC1-EN)") (class "Default")
      (node (ref "IC1") (pin "8") (pinfunction "EN_8") (pintype "passive"))
      (node (ref "P14") (pin "2") (pinfunction "2_2") (pintype "passive"))
    )
    (net (code "84") (name "Net-(IC2-EN)") (class "Default")
      (node (ref "IC2") (pin "8") (pinfunction "EN_8") (pintype "passive"))
      (node (ref "P16") (pin "2") (pinfunction "2_2") (pintype "passive"))
    )
    (net (code "85") (name "Net-(IC3-EN)") (class "Default")
      (node (ref "IC3") (pin "8") (pinfunction "EN_8") (pintype "passive"))
      (node (ref "P17") (pin "2") (pinfunction "2_2") (pintype "passive"))
    )
    (net (code "86") (name "Net-(IC4-EN)") (class "Default")
      (node (ref "IC4") (pin "8") (pinfunction "EN_8") (pintype "passive"))
      (node (ref "P20") (pin "2") (pinfunction "2_2") (pintype "passive"))
    )
    (net (code "87") (name "Net-(IC5-EN)") (class "Default")
      (node (ref "IC5") (pin "8") (pinfunction "EN_8") (pintype "passive"))
      (node (ref "P22") (pin "2") (pinfunction "2_2") (pintype "passive"))
    )
    (net (code "88") (name "Net-(IC6-EN)") (class "Default")
      (node (ref "IC6") (pin "8") (pinfunction "EN_8") (pintype "passive"))
      (node (ref "P23") (pin "2") (pinfunction "2_2") (pintype "passive"))
    )
    (net (code "89") (name "Net-(U8-1DIR)") (class "Default")
      (node (ref "P11") (pin "1") (pinfunction "1_1") (pintype "passive"))
      (node (ref "U8") (pin "1") (pinfunction "1DIR_1") (pintype "input"))
    )
    (net (code "90") (name "Net-(U8-1~{OE})") (class "Default")
      (node (ref "P13") (pin "2") (pinfunction "2_2") (pintype "passive"))
      (node (ref "U8") (pin "25") (pinfunction "2~{OE}_25") (pintype "passive"))
      (node (ref "U8") (pin "48") (pinfunction "1~{OE}_48") (pintype "passive"))
    )
    (net (code "91") (name "Net-(U8-2DIR)") (class "Default")
      (node (ref "P12") (pin "2") (pinfunction "2_2") (pintype "passive"))
      (node (ref "U8") (pin "24") (pinfunction "2DIR_24") (pintype "input"))
    )
    (net (code "92") (name "unconnected-(IC1-NC_1-Pad6)") (class "Default")
      (node (ref "IC1") (pin "6") (pinfunction "NC_1_6") (pintype "passive"))
    )
    (net (code "93") (name "unconnected-(IC1-NC_2-Pad9)") (class "Default")
      (node (ref "IC1") (pin "9") (pinfunction "NC_2_9") (pintype "passive"))
    )
    (net (code "94") (name "unconnected-(IC2-NC_1-Pad6)") (class "Default")
      (node (ref "IC2") (pin "6") (pinfunction "NC_1_6") (pintype "passive"))
    )
    (net (code "95") (name "unconnected-(IC2-NC_2-Pad9)") (class "Default")
      (node (ref "IC2") (pin "9") (pinfunction "NC_2_9") (pintype "passive"))
    )
    (net (code "96") (name "unconnected-(IC3-A3-Pad4)") (class "Default")
      (node (ref "IC3") (pin "4") (pinfunction "A3_4") (pintype "passive"))
    )
    (net (code "97") (name "unconnected-(IC3-A4-Pad5)") (class "Default")
      (node (ref "IC3") (pin "5") (pinfunction "A4_5") (pintype "passive"))
    )
    (net (code "98") (name "unconnected-(IC3-B3-Pad11)") (class "Default")
      (node (ref "IC3") (pin "11") (pinfunction "B3_11") (pintype "passive"))
    )
    (net (code "99") (name "unconnected-(IC3-B4-Pad10)") (class "Default")
      (node (ref "IC3") (pin "10") (pinfunction "B4_10") (pintype "passive"))
    )
    (net (code "100") (name "unconnected-(IC3-NC_1-Pad6)") (class "Default")
      (node (ref "IC3") (pin "6") (pinfunction "NC_1_6") (pintype "passive"))
    )
    (net (code "101") (name "unconnected-(IC3-NC_2-Pad9)") (class "Default")
      (node (ref "IC3") (pin "9") (pinfunction "NC_2_9") (pintype "passive"))
    )
    (net (code "102") (name "unconnected-(IC4-NC_1-Pad6)") (class "Default")
      (node (ref "IC4") (pin "6") (pinfunction "NC_1_6") (pintype "passive"))
    )
    (net (code "103") (name "unconnected-(IC4-NC_2-Pad9)") (class "Default")
      (node (ref "IC4") (pin "9") (pinfunction "NC_2_9") (pintype "passive"))
    )
    (net (code "104") (name "unconnected-(IC5-NC_1-Pad6)") (class "Default")
      (node (ref "IC5") (pin "6") (pinfunction "NC_1_6") (pintype "passive"))
    )
    (net (code "105") (name "unconnected-(IC5-NC_2-Pad9)") (class "Default")
      (node (ref "IC5") (pin "9") (pinfunction "NC_2_9") (pintype "passive"))
    )
    (net (code "106") (name "unconnected-(IC6-NC_1-Pad6)") (class "Default")
      (node (ref "IC6") (pin "6") (pinfunction "NC_1_6") (pintype "passive"))
    )
    (net (code "107") (name "unconnected-(IC6-NC_2-Pad9)") (class "Default")
      (node (ref "IC6") (pin "9") (pinfunction "NC_2_9") (pintype "passive"))
    )
    (net (code "108") (name "unconnected-(P8-Pad6)") (class "Default")
      (node (ref "P8") (pin "6") (pinfunction "6_6") (pintype "passive+no_connect"))
    )
    (net (code "109") (name "unconnected-(P9-Pad1)") (class "Default")
      (node (ref "P9") (pin "1") (pinfunction "1_1") (pintype "passive"))
    )
    (net (code "110") (name "unconnected-(P9-Pad2)") (class "Default")
      (node (ref "P9") (pin "2") (pinfunction "2_2") (pintype "passive"))
    )
    (net (code "111") (name "unconnected-(P9-Pad4)") (class "Default")
      (node (ref "P9") (pin "4") (pinfunction "4_4") (pintype "passive"))
    )
    (net (code "112") (name "unconnected-(P9-Pad6)") (class "Default")
      (node (ref "P9") (pin "6") (pinfunction "6_6") (pintype "passive"))
    )
    (net (code "113") (name "unconnected-(P9-Pad7)") (class "Default")
      (node (ref "P9") (pin "7") (pinfunction "7_7") (pintype "passive"))
    )
    (net (code "114") (name "unconnected-(P9-Pad8)") (class "Default")
      (node (ref "P9") (pin "8") (pinfunction "8_8") (pintype "passive"))
    )
    (net (code "115") (name "unconnected-(P9-Pad9)") (class "Default")
      (node (ref "P9") (pin "9") (pinfunction "9_9") (pintype "passive"))
    )
    (net (code "116") (name "unconnected-(P9-Pad10)") (class "Default")
      (node (ref "P9") (pin "10") (pinfunction "10_10") (pintype "passive"))
    )
    (net (code "117") (name "unconnected-(P9-Pad11)") (class "Default")
      (node (ref "P9") (pin "11") (pinfunction "11_11") (pintype "passive"))
    )
    (net (code "118") (name "unconnected-(P9-Pad12)") (class "Default")
      (node (ref "P9") (pin "12") (pinfunction "12_12") (pintype "passive"))
    )
    (net (code "119") (name "unconnected-(P9-Pad13)") (class "Default")
      (node (ref "P9") (pin "13") (pinfunction "13_13") (pintype "passive"))
    )
    (net (code "120") (name "unconnected-(P9-Pad14)") (class "Default")
      (node (ref "P9") (pin "14") (pinfunction "14_14") (pintype "passive"))
    )
    (net (code "121") (name "unconnected-(P9-Pad15)") (class "Default")
      (node (ref "P9") (pin "15") (pinfunction "15_15") (pintype "passive"))
    )
    (net (code "122") (name "unconnected-(P9-Pad16)") (class "Default")
      (node (ref "P9") (pin "16") (pinfunction "16_16") (pintype "passive"))
    )
    (net (code "123") (name "unconnected-(P10-Pad1)") (class "Default")
      (node (ref "P10") (pin "1") (pinfunction "1_1") (pintype "passive+no_connect"))
    )
    (net (code "124") (name "unconnected-(P10-Pad2)") (class "Default")
      (node (ref "P10") (pin "2") (pinfunction "2_2") (pintype "passive+no_connect"))
    )
    (net (code "125") (name "unconnected-(P10-Pad3)") (class "Default")
      (node (ref "P10") (pin "3") (pinfunction "3_3") (pintype "passive+no_connect"))
    )
    (net (code "126") (name "unconnected-(P10-Pad4)") (class "Default")
      (node (ref "P10") (pin "4") (pinfunction "4_4") (pintype "passive+no_connect"))
    )
    (net (code "127") (name "unconnected-(P15-Pad2)") (class "Default")
      (node (ref "P15") (pin "2") (pinfunction "2_2") (pintype "passive"))
    )
    (net (code "128") (name "unconnected-(P15-Pad3)") (class "Default")
      (node (ref "P15") (pin "3") (pinfunction "3_3") (pintype "passive+no_connect"))
    )
    (net (code "129") (name "unconnected-(P15-Pad17)") (class "Default")
      (node (ref "P15") (pin "17") (pinfunction "17_17") (pintype "passive"))
    )
    (net (code "130") (name "unconnected-(P15-Pad19)") (class "Default")
      (node (ref "P15") (pin "19") (pinfunction "19_19") (pintype "passive"))
    )
  )
)
